# EP2.net
KiCad netlist of a schematic drawn in EAGLE
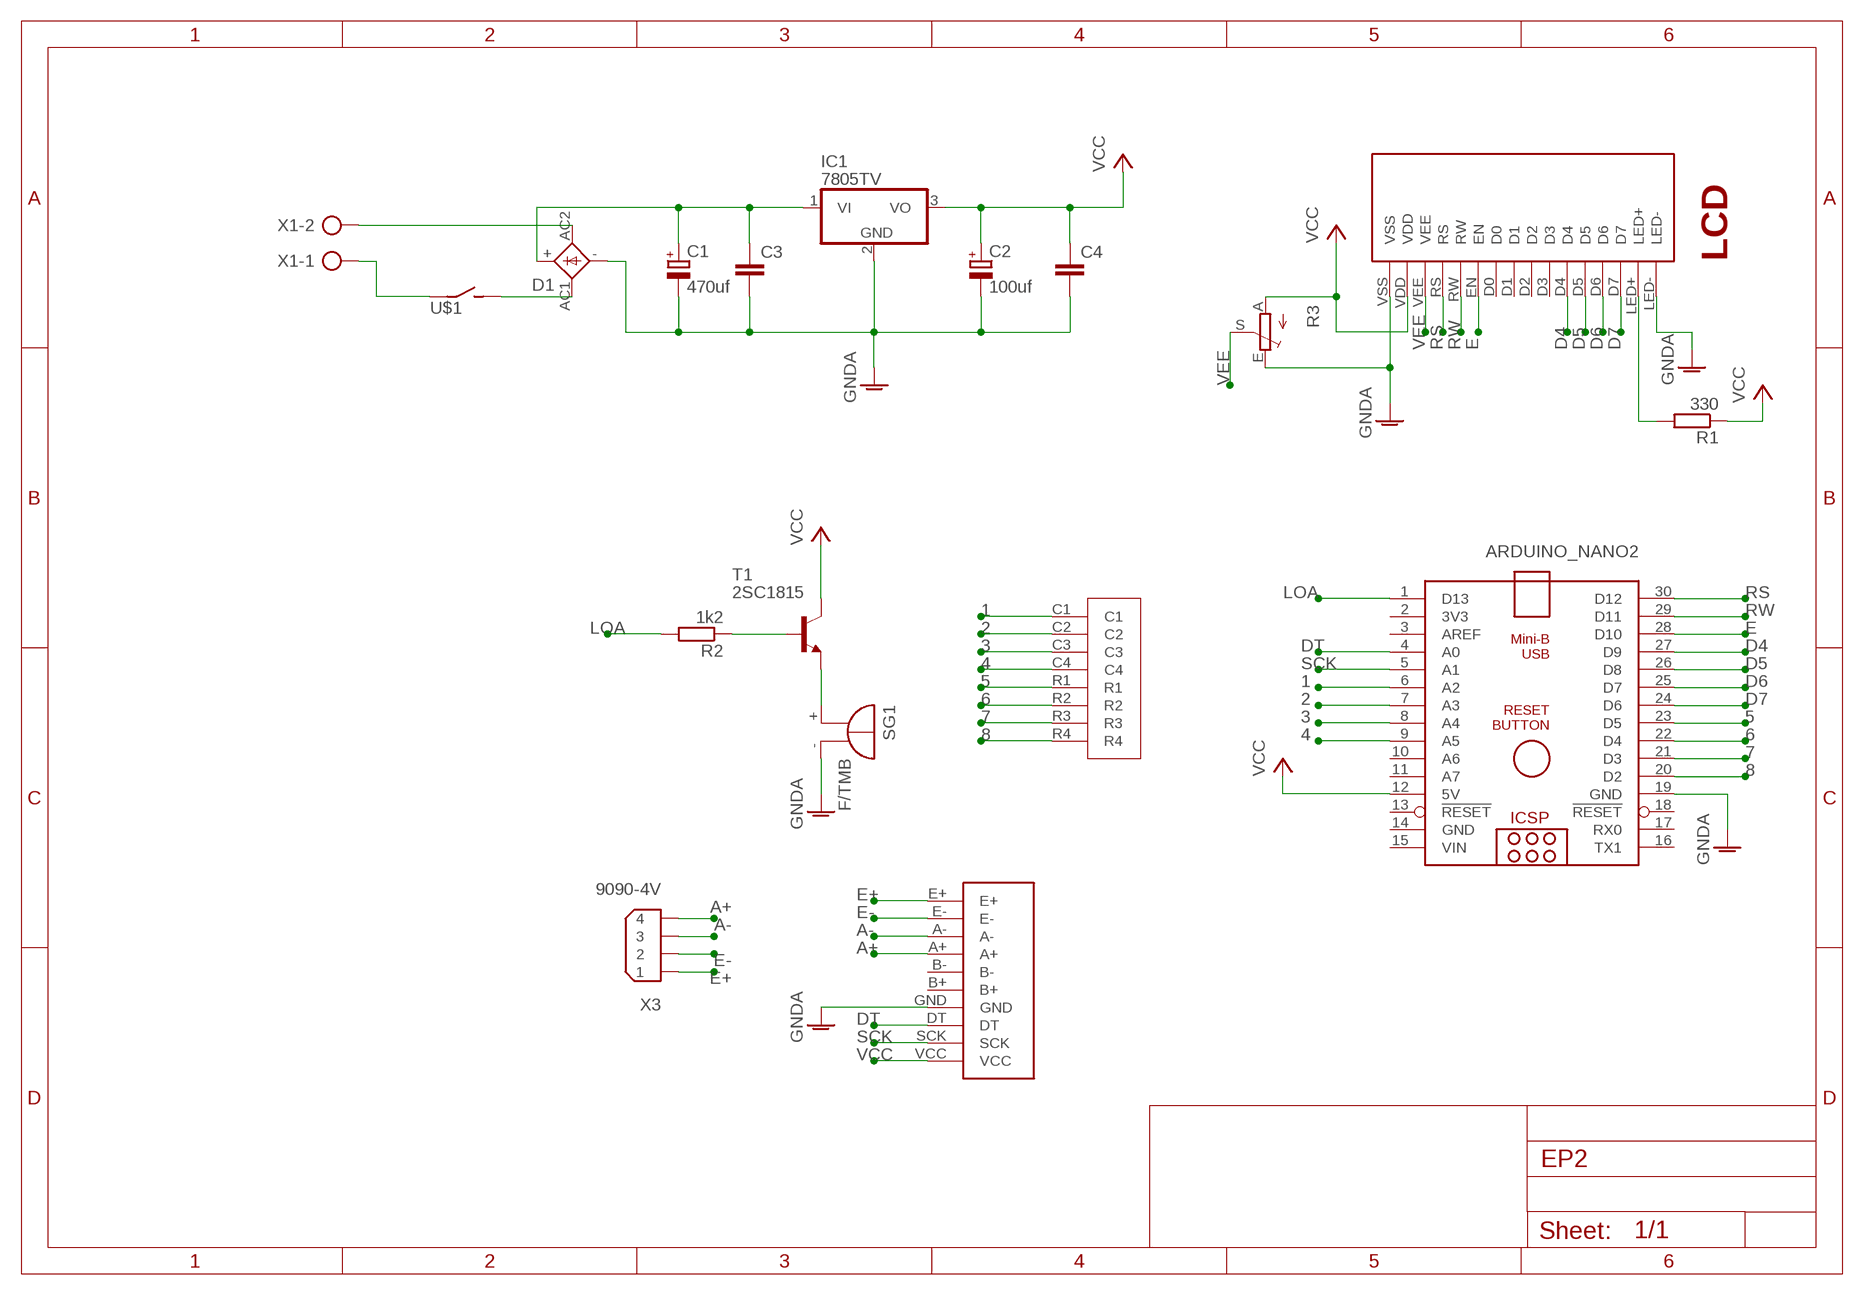
[diagram p0: schematic, sheet 1]

(export (version "E")
  (design (tool "Eeschema 10.0.6"))
  (components
    (comp (ref "ARDUINO_NANO2")
      (value "ARDUINO_NANO")
      (footprint "eagle-import:ARDUINO_NANO")
      (libsource (lib "eagle-import") (part "ARDUINO_NANO"))
    )
    (comp (ref "C1")
      (value "470uf")
      (footprint "eagle-import:E3,5-8")
      (libsource (lib "eagle-import") (part "CPOL-EUE3.5-8"))
    )
    (comp (ref "C2")
      (value "100uf")
      (footprint "eagle-import:E2-5")
      (libsource (lib "eagle-import") (part "CPOL-EUE2-5"))
    )
    (comp (ref "C3")
      (value "C-EU025-024X044")
      (footprint "eagle-import:C025-024X044")
      (libsource (lib "eagle-import") (part "C-EU025-024X044"))
    )
    (comp (ref "C4")
      (value "C-EU025-024X044")
      (footprint "eagle-import:C025-024X044")
      (libsource (lib "eagle-import") (part "C-EU025-024X044"))
    )
    (comp (ref "D1")
      (value "2KBP")
      (footprint "eagle-import:2KBP")
      (libsource (lib "eagle-import") (part "2KBP"))
    )
    (comp (ref "IC1")
      (value "7805TV")
      (footprint "eagle-import:TO220V")
      (libsource (lib "eagle-import") (part "78TV05"))
    )
    (comp (ref "LCD")
      (value "LCD20X4")
      (footprint "eagle-import:LCD20X4")
      (libsource (lib "eagle-import") (part "LCD20X4"))
    )
    (comp (ref "M1")
      (value "MACHMAUXANH")
      (footprint "eagle-import:MACHMAUXANH")
      (libsource (lib "eagle-import") (part "MACHMAUXANH"))
    )
    (comp (ref "R1")
      (value "330")
      (footprint "eagle-import:0207_10")
      (libsource (lib "eagle-import") (part "R-EU_0207/10"))
    )
    (comp (ref "R2")
      (value "1k2")
      (footprint "eagle-import:0207_10")
      (libsource (lib "eagle-import") (part "R-EU_0207/10"))
    )
    (comp (ref "R3")
      (value "TRIM_EU-S64W")
      (footprint "eagle-import:S64W")
      (libsource (lib "eagle-import") (part "TRIM_EU-S64W"))
    )
    (comp (ref "SG1")
      (value "F/TMB")
      (footprint "eagle-import:F_TMB")
      (libsource (lib "eagle-import") (part "F/TMB"))
    )
    (comp (ref "T1")
      (value "2SC1815")
      (footprint "eagle-import:TO92-ECB")
      (libsource (lib "eagle-import") (part "2SC1815"))
    )
    (comp (ref "U$1")
      (value "CONG_TAC")
      (footprint "eagle-import:CONG_TAC")
      (libsource (lib "eagle-import") (part "CONG_TAC"))
    )
    (comp (ref "U$2")
      (value "MA_TRAN_PHIM")
      (footprint "eagle-import:MA_TRAN_PHIM")
      (libsource (lib "eagle-import") (part "MA_TRAN_PHIM"))
    )
    (comp (ref "X1")
      (value "AK300/2")
      (footprint "eagle-import:AK300_2")
      (libsource (lib "eagle-import") (part "AK300/2"))
    )
    (comp (ref "X3")
      (value "9090-4V")
      (footprint "eagle-import:9090-4V")
      (libsource (lib "eagle-import") (part "9090-4V"))
    )
  )
  (nets
    (net (code "1") (name "/1") (class "Default")
      (node (ref "ARDUINO_NANO2") (pin "6") (pinfunction "A2_6") (pintype "bidirectional"))
      (node (ref "U$2") (pin "C1") (pinfunction "C1_C1") (pintype "bidirectional"))
    )
    (net (code "2") (name "/2") (class "Default")
      (node (ref "ARDUINO_NANO2") (pin "7") (pinfunction "A3_7") (pintype "bidirectional"))
      (node (ref "U$2") (pin "C2") (pinfunction "C2_C2") (pintype "bidirectional"))
    )
    (net (code "3") (name "/3") (class "Default")
      (node (ref "ARDUINO_NANO2") (pin "8") (pinfunction "A4_8") (pintype "bidirectional"))
      (node (ref "U$2") (pin "C3") (pinfunction "C3_C3") (pintype "bidirectional"))
    )
    (net (code "4") (name "/4") (class "Default")
      (node (ref "ARDUINO_NANO2") (pin "9") (pinfunction "A5_9") (pintype "bidirectional"))
      (node (ref "U$2") (pin "C4") (pinfunction "C4_C4") (pintype "bidirectional"))
    )
    (net (code "5") (name "/5") (class "Default")
      (node (ref "ARDUINO_NANO2") (pin "23") (pinfunction "D5_23") (pintype "bidirectional"))
      (node (ref "U$2") (pin "R1") (pinfunction "R1_R1") (pintype "bidirectional"))
    )
    (net (code "6") (name "/6") (class "Default")
      (node (ref "ARDUINO_NANO2") (pin "22") (pinfunction "D4_22") (pintype "bidirectional"))
      (node (ref "U$2") (pin "R2") (pinfunction "R2_R2") (pintype "bidirectional"))
    )
    (net (code "7") (name "/7") (class "Default")
      (node (ref "ARDUINO_NANO2") (pin "21") (pinfunction "D3_21") (pintype "bidirectional"))
      (node (ref "U$2") (pin "R3") (pinfunction "R3_R3") (pintype "bidirectional"))
    )
    (net (code "8") (name "/8") (class "Default")
      (node (ref "ARDUINO_NANO2") (pin "20") (pinfunction "D2_20") (pintype "bidirectional"))
      (node (ref "U$2") (pin "R4") (pinfunction "R4_R4") (pintype "bidirectional"))
    )
    (net (code "9") (name "/A+") (class "Default")
      (node (ref "M1") (pin "A+") (pinfunction "A+_A+") (pintype "bidirectional"))
      (node (ref "X3") (pin "4") (pinfunction "4_4") (pintype "passive"))
    )
    (net (code "10") (name "/A-") (class "Default")
      (node (ref "M1") (pin "A-") (pinfunction "A-_A-") (pintype "bidirectional"))
      (node (ref "X3") (pin "3") (pinfunction "3_3") (pintype "passive"))
    )
    (net (code "11") (name "/D4") (class "Default")
      (node (ref "ARDUINO_NANO2") (pin "27") (pinfunction "D9_27") (pintype "bidirectional"))
      (node (ref "LCD") (pin "D4") (pinfunction "D4_D4") (pintype "bidirectional"))
    )
    (net (code "12") (name "/D5") (class "Default")
      (node (ref "ARDUINO_NANO2") (pin "26") (pinfunction "D8_26") (pintype "bidirectional"))
      (node (ref "LCD") (pin "D5") (pinfunction "D5_D5") (pintype "bidirectional"))
    )
    (net (code "13") (name "/D6") (class "Default")
      (node (ref "ARDUINO_NANO2") (pin "25") (pinfunction "D7_25") (pintype "bidirectional"))
      (node (ref "LCD") (pin "D6") (pinfunction "D6_D6") (pintype "bidirectional"))
    )
    (net (code "14") (name "/D7") (class "Default")
      (node (ref "ARDUINO_NANO2") (pin "24") (pinfunction "D6_24") (pintype "bidirectional"))
      (node (ref "LCD") (pin "D7") (pinfunction "D7_D7") (pintype "bidirectional"))
    )
    (net (code "15") (name "/DT") (class "Default")
      (node (ref "ARDUINO_NANO2") (pin "4") (pinfunction "A0_4") (pintype "bidirectional"))
      (node (ref "M1") (pin "DT") (pinfunction "DT_DT") (pintype "bidirectional"))
    )
    (net (code "16") (name "/E") (class "Default")
      (node (ref "ARDUINO_NANO2") (pin "28") (pinfunction "D10_28") (pintype "bidirectional"))
      (node (ref "LCD") (pin "EN") (pinfunction "EN_EN") (pintype "bidirectional"))
    )
    (net (code "17") (name "/E+") (class "Default")
      (node (ref "M1") (pin "E+") (pinfunction "E+_E+") (pintype "bidirectional"))
      (node (ref "X3") (pin "1") (pinfunction "1_1") (pintype "passive"))
    )
    (net (code "18") (name "/E-") (class "Default")
      (node (ref "M1") (pin "E-") (pinfunction "E-_E-") (pintype "bidirectional"))
      (node (ref "X3") (pin "2") (pinfunction "2_2") (pintype "passive"))
    )
    (net (code "19") (name "/GND") (class "Default")
      (node (ref "ARDUINO_NANO2") (pin "14") (pinfunction "GND_14") (pintype "power_in"))
    )
    (net (code "20") (name "/LOA") (class "Default")
      (node (ref "ARDUINO_NANO2") (pin "1") (pinfunction "D13_1") (pintype "bidirectional"))
      (node (ref "R2") (pin "2") (pinfunction "2_2") (pintype "passive"))
    )
    (net (code "21") (name "/RS") (class "Default")
      (node (ref "ARDUINO_NANO2") (pin "30") (pinfunction "D12_30") (pintype "bidirectional"))
      (node (ref "LCD") (pin "RS") (pinfunction "RS_RS") (pintype "bidirectional"))
    )
    (net (code "22") (name "/RW") (class "Default")
      (node (ref "ARDUINO_NANO2") (pin "29") (pinfunction "D11_29") (pintype "bidirectional"))
      (node (ref "LCD") (pin "RW") (pinfunction "RW_RW") (pintype "bidirectional"))
    )
    (net (code "23") (name "/SCK") (class "Default")
      (node (ref "ARDUINO_NANO2") (pin "5") (pinfunction "A1_5") (pintype "bidirectional"))
      (node (ref "M1") (pin "SCK") (pinfunction "SCK_SCK") (pintype "bidirectional"))
    )
    (net (code "24") (name "/VEE") (class "Default")
      (node (ref "LCD") (pin "VEE") (pinfunction "VEE_VEE") (pintype "bidirectional"))
      (node (ref "R3") (pin "S") (pinfunction "S_S") (pintype "passive"))
    )
    (net (code "25") (name "/VIN") (class "Default")
      (node (ref "ARDUINO_NANO2") (pin "15") (pinfunction "VIN_15") (pintype "power_in"))
    )
    (net (code "26") (name "GNDA") (class "Default")
      (node (ref "ARDUINO_NANO2") (pin "19") (pinfunction "GND_19") (pintype "power_in"))
      (node (ref "C1") (pin "-") (pinfunction "-_-") (pintype "passive"))
      (node (ref "C2") (pin "-") (pinfunction "-_-") (pintype "passive"))
      (node (ref "C3") (pin "2") (pinfunction "2_2") (pintype "passive"))
      (node (ref "C4") (pin "2") (pinfunction "2_2") (pintype "passive"))
      (node (ref "D1") (pin "-") (pinfunction "-_-") (pintype "passive"))
      (node (ref "IC1") (pin "2") (pinfunction "GND_2") (pintype "passive"))
      (node (ref "LCD") (pin "LED-") (pinfunction "LED-_LED-") (pintype "bidirectional"))
      (node (ref "LCD") (pin "VSS") (pinfunction "VSS_VSS") (pintype "bidirectional"))
      (node (ref "M1") (pin "GND") (pinfunction "GND_GND") (pintype "bidirectional"))
      (node (ref "R3") (pin "E") (pinfunction "E_E") (pintype "passive"))
      (node (ref "SG1") (pin "-") (pinfunction "-_-") (pintype "passive"))
    )
    (net (code "27") (name "Net-(IC1-VI)") (class "Default")
      (node (ref "C1") (pin "+") (pinfunction "+_+") (pintype "passive"))
      (node (ref "C3") (pin "1") (pinfunction "1_1") (pintype "passive"))
      (node (ref "D1") (pin "+") (pinfunction "+_+") (pintype "passive"))
      (node (ref "IC1") (pin "1") (pinfunction "VI_1") (pintype "input"))
    )
    (net (code "28") (name "Net-(LCD-PadLED+)") (class "Default")
      (node (ref "LCD") (pin "LED+") (pinfunction "LED+_LED+") (pintype "bidirectional"))
      (node (ref "R1") (pin "2") (pinfunction "2_2") (pintype "passive"))
    )
    (net (code "29") (name "Net-(R2-Pad1)") (class "Default")
      (node (ref "R2") (pin "1") (pinfunction "1_1") (pintype "passive"))
      (node (ref "T1") (pin "B") (pinfunction "B_B") (pintype "passive"))
    )
    (net (code "30") (name "Net-(SG1-Pad+)") (class "Default")
      (node (ref "SG1") (pin "+") (pinfunction "+_+") (pintype "passive"))
      (node (ref "T1") (pin "E") (pinfunction "E_E") (pintype "passive"))
    )
    (net (code "31") (name "Net-(U$1-1)") (class "Default")
      (node (ref "U$1") (pin "P$1") (pinfunction "1_P$1") (pintype "bidirectional"))
      (node (ref "X1") (pin "1") (pinfunction "KL_1") (pintype "passive"))
    )
    (net (code "32") (name "Net-(U$1-2)") (class "Default")
      (node (ref "D1") (pin "AC1") (pinfunction "AC1_AC1") (pintype "passive"))
      (node (ref "U$1") (pin "P$2") (pinfunction "2_P$2") (pintype "bidirectional"))
    )
    (net (code "33") (name "Net-(X1B-KL)") (class "Default")
      (node (ref "D1") (pin "AC2") (pinfunction "AC2_AC2") (pintype "passive"))
      (node (ref "X1") (pin "2") (pinfunction "KL_2") (pintype "passive"))
    )
    (net (code "34") (name "VCC") (class "Default")
      (node (ref "ARDUINO_NANO2") (pin "12") (pinfunction "5V_12") (pintype "power_in"))
      (node (ref "C2") (pin "+") (pinfunction "+_+") (pintype "passive"))
      (node (ref "C4") (pin "1") (pinfunction "1_1") (pintype "passive"))
      (node (ref "IC1") (pin "3") (pinfunction "VO_3") (pintype "passive"))
      (node (ref "LCD") (pin "VDD") (pinfunction "VDD_VDD") (pintype "bidirectional"))
      (node (ref "M1") (pin "VCC") (pinfunction "VCC_VCC") (pintype "bidirectional"))
      (node (ref "R1") (pin "1") (pinfunction "1_1") (pintype "passive"))
      (node (ref "R3") (pin "A") (pinfunction "A_A") (pintype "passive"))
      (node (ref "T1") (pin "C") (pinfunction "C_C") (pintype "passive"))
    )
    (net (code "35") (name "unconnected-(ARDUINO_NANO2-3V3-Pad2)") (class "Default")
      (node (ref "ARDUINO_NANO2") (pin "2") (pinfunction "3V3_2") (pintype "output"))
    )
    (net (code "36") (name "unconnected-(ARDUINO_NANO2-A6-Pad10)") (class "Default")
      (node (ref "ARDUINO_NANO2") (pin "10") (pinfunction "A6_10") (pintype "bidirectional"))
    )
    (net (code "37") (name "unconnected-(ARDUINO_NANO2-A7-Pad11)") (class "Default")
      (node (ref "ARDUINO_NANO2") (pin "11") (pinfunction "A7_11") (pintype "bidirectional"))
    )
    (net (code "38") (name "unconnected-(ARDUINO_NANO2-AREF-Pad3)") (class "Default")
      (node (ref "ARDUINO_NANO2") (pin "3") (pinfunction "AREF_3") (pintype "input"))
    )
    (net (code "39") (name "unconnected-(ARDUINO_NANO2-RX0-Pad17)") (class "Default")
      (node (ref "ARDUINO_NANO2") (pin "17") (pinfunction "RX0_17") (pintype "bidirectional"))
    )
    (net (code "40") (name "unconnected-(ARDUINO_NANO2-TX1-Pad16)") (class "Default")
      (node (ref "ARDUINO_NANO2") (pin "16") (pinfunction "TX1_16") (pintype "bidirectional"))
    )
    (net (code "41") (name "unconnected-(ARDUINO_NANO2-~{RESET}-Pad13)") (class "Default")
      (node (ref "ARDUINO_NANO2") (pin "13") (pinfunction "~{RESET}_13") (pintype "input"))
    )
    (net (code "42") (name "unconnected-(ARDUINO_NANO2-~{RESET}-Pad18)") (class "Default")
      (node (ref "ARDUINO_NANO2") (pin "18") (pinfunction "~{RESET}_18") (pintype "input"))
    )
    (net (code "43") (name "unconnected-(LCD-PadD0)") (class "Default")
      (node (ref "LCD") (pin "D0") (pinfunction "D0_D0") (pintype "bidirectional"))
    )
    (net (code "44") (name "unconnected-(LCD-PadD1)") (class "Default")
      (node (ref "LCD") (pin "D1") (pinfunction "D1_D1") (pintype "bidirectional"))
    )
    (net (code "45") (name "unconnected-(LCD-PadD2)") (class "Default")
      (node (ref "LCD") (pin "D2") (pinfunction "D2_D2") (pintype "bidirectional"))
    )
    (net (code "46") (name "unconnected-(LCD-PadD3)") (class "Default")
      (node (ref "LCD") (pin "D3") (pinfunction "D3_D3") (pintype "bidirectional"))
    )
    (net (code "47") (name "unconnected-(M1-PadB+)") (class "Default")
      (node (ref "M1") (pin "B+") (pinfunction "B+_B+") (pintype "bidirectional"))
    )
    (net (code "48") (name "unconnected-(M1-PadB-)") (class "Default")
      (node (ref "M1") (pin "B-") (pinfunction "B-_B-") (pintype "bidirectional"))
    )
  )
)
